# USB3300.net
KiCad netlist of a schematic drawn in EAGLE
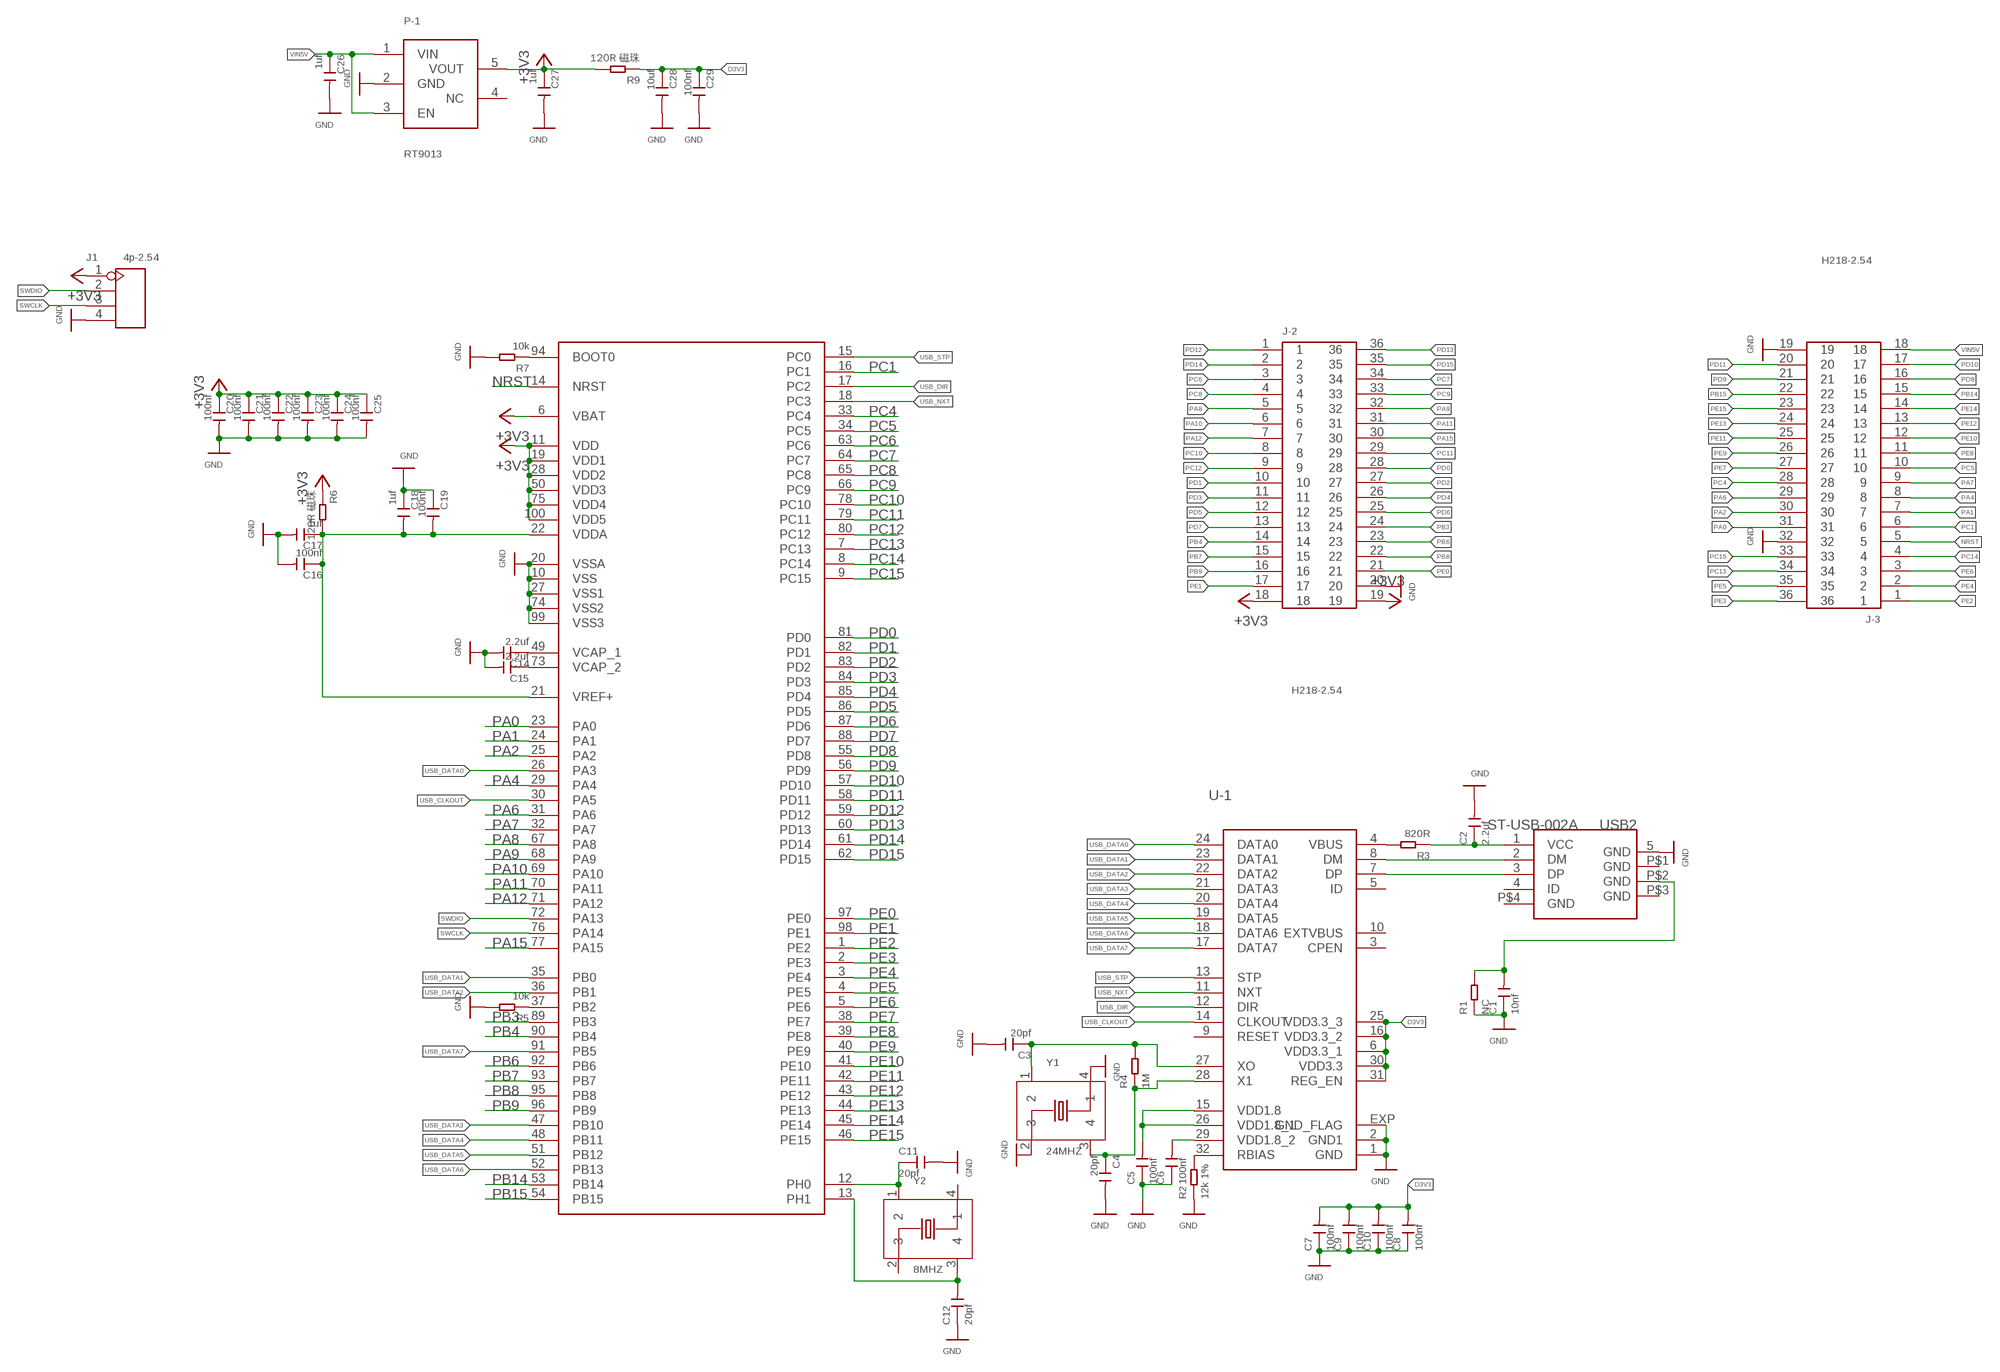
[diagram p0: schematic, sheet 1]

(export (version "E")
  (design (tool "Eeschema 10.0.6"))
  (components
    (comp (ref "C1")
      (value "10nf")
      (footprint "eagle-import:C0603")
      (libsource (lib "eagle-import") (part "CERAMIC-0.5PF-50V-0.1PF-NPO(0603)"))
    )
    (comp (ref "C2")
      (value "2.2uf")
      (footprint "eagle-import:C0603")
      (libsource (lib "eagle-import") (part "CERAMIC-0.5PF-50V-0.1PF-NPO(0603)"))
    )
    (comp (ref "C3")
      (value "20pf")
      (footprint "eagle-import:C0603")
      (libsource (lib "eagle-import") (part "CERAMIC-0.5PF-50V-0.1PF-NPO(0603)"))
    )
    (comp (ref "C4")
      (value "20pf")
      (footprint "eagle-import:C0603")
      (libsource (lib "eagle-import") (part "CERAMIC-0.5PF-50V-0.1PF-NPO(0603)"))
    )
    (comp (ref "C5")
      (value "100nf")
      (footprint "eagle-import:C0603")
      (libsource (lib "eagle-import") (part "CERAMIC-0.5PF-50V-0.1PF-NPO(0603)"))
    )
    (comp (ref "C6")
      (value "100nf")
      (footprint "eagle-import:C0603")
      (libsource (lib "eagle-import") (part "CERAMIC-0.5PF-50V-0.1PF-NPO(0603)"))
    )
    (comp (ref "C7")
      (value "100nf")
      (footprint "eagle-import:C0603")
      (libsource (lib "eagle-import") (part "CERAMIC-0.5PF-50V-0.1PF-NPO(0603)"))
    )
    (comp (ref "C8")
      (value "100nf")
      (footprint "eagle-import:C0603")
      (libsource (lib "eagle-import") (part "CERAMIC-0.5PF-50V-0.1PF-NPO(0603)"))
    )
    (comp (ref "C9")
      (value "100nf")
      (footprint "eagle-import:C0603")
      (libsource (lib "eagle-import") (part "CERAMIC-0.5PF-50V-0.1PF-NPO(0603)"))
    )
    (comp (ref "C10")
      (value "100nf")
      (footprint "eagle-import:C0603")
      (libsource (lib "eagle-import") (part "CERAMIC-0.5PF-50V-0.1PF-NPO(0603)"))
    )
    (comp (ref "C11")
      (value "20pf")
      (footprint "eagle-import:C0603")
      (libsource (lib "eagle-import") (part "CERAMIC-0.5PF-50V-0.1PF-NPO(0603)"))
    )
    (comp (ref "C12")
      (value "20pf")
      (footprint "eagle-import:C0603")
      (libsource (lib "eagle-import") (part "CERAMIC-0.5PF-50V-0.1PF-NPO(0603)"))
    )
    (comp (ref "C14")
      (value "2.2uf")
      (footprint "eagle-import:C0603")
      (libsource (lib "eagle-import") (part "CERAMIC-0.5PF-50V-0.1PF-NPO(0603)"))
    )
    (comp (ref "C15")
      (value "2.2uf")
      (footprint "eagle-import:C0603")
      (libsource (lib "eagle-import") (part "CERAMIC-0.5PF-50V-0.1PF-NPO(0603)"))
    )
    (comp (ref "C16")
      (value "100nf")
      (footprint "eagle-import:C0603")
      (libsource (lib "eagle-import") (part "CERAMIC-0.5PF-50V-0.1PF-NPO(0603)"))
    )
    (comp (ref "C17")
      (value "1uf")
      (footprint "eagle-import:C0603")
      (libsource (lib "eagle-import") (part "CERAMIC-0.5PF-50V-0.1PF-NPO(0603)"))
    )
    (comp (ref "C18")
      (value "1uf")
      (footprint "eagle-import:C0603")
      (libsource (lib "eagle-import") (part "CERAMIC-0.5PF-50V-0.1PF-NPO(0603)"))
    )
    (comp (ref "C19")
      (value "100nf")
      (footprint "eagle-import:C0603")
      (libsource (lib "eagle-import") (part "CERAMIC-0.5PF-50V-0.1PF-NPO(0603)"))
    )
    (comp (ref "C20")
      (value "100nf")
      (footprint "eagle-import:C0603")
      (libsource (lib "eagle-import") (part "CERAMIC-0.5PF-50V-0.1PF-NPO(0603)"))
    )
    (comp (ref "C21")
      (value "100nf")
      (footprint "eagle-import:C0603")
      (libsource (lib "eagle-import") (part "CERAMIC-0.5PF-50V-0.1PF-NPO(0603)"))
    )
    (comp (ref "C22")
      (value "100nf")
      (footprint "eagle-import:C0603")
      (libsource (lib "eagle-import") (part "CERAMIC-0.5PF-50V-0.1PF-NPO(0603)"))
    )
    (comp (ref "C23")
      (value "100nf")
      (footprint "eagle-import:C0603")
      (libsource (lib "eagle-import") (part "CERAMIC-0.5PF-50V-0.1PF-NPO(0603)"))
    )
    (comp (ref "C24")
      (value "100nf")
      (footprint "eagle-import:C0603")
      (libsource (lib "eagle-import") (part "CERAMIC-0.5PF-50V-0.1PF-NPO(0603)"))
    )
    (comp (ref "C25")
      (value "100nf")
      (footprint "eagle-import:C0603")
      (libsource (lib "eagle-import") (part "CERAMIC-0.5PF-50V-0.1PF-NPO(0603)"))
    )
    (comp (ref "C26")
      (value "1uf")
      (footprint "eagle-import:C0603")
      (libsource (lib "eagle-import") (part "CERAMIC-0.5PF-50V-0.1PF-NPO(0603)"))
    )
    (comp (ref "C27")
      (value "1uf")
      (footprint "eagle-import:C0603")
      (libsource (lib "eagle-import") (part "CERAMIC-0.5PF-50V-0.1PF-NPO(0603)"))
    )
    (comp (ref "C28")
      (value "10uf")
      (footprint "eagle-import:C0603")
      (libsource (lib "eagle-import") (part "CERAMIC-0.5PF-50V-0.1PF-NPO(0603)"))
    )
    (comp (ref "C29")
      (value "100nf")
      (footprint "eagle-import:C0603")
      (libsource (lib "eagle-import") (part "CERAMIC-0.5PF-50V-0.1PF-NPO(0603)"))
    )
    (comp (ref "J-2")
      (value "H218-2.54")
      (footprint "eagle-import:H2X18-2.54")
      (libsource (lib "eagle-import") (part "H218-2.54"))
    )
    (comp (ref "J-3")
      (value "H218-2.54")
      (footprint "eagle-import:H2X18-2.54")
      (libsource (lib "eagle-import") (part "H218-2.54"))
    )
    (comp (ref "J1")
      (value "4p-2.54")
      (footprint "eagle-import:H4-2.54")
      (fields (field (name "MPN") "F185-1104A1BSYA1"))
      (libsource (lib "eagle-import") (part "DIP-BLACK-FEMALE-HEADER-VERT(4P-2.54)"))
    )
    (comp (ref "P-1")
      (value "RT9013")
      (footprint "eagle-import:SOT23-5")
      (libsource (lib "eagle-import") (part "RT9013"))
    )
    (comp (ref "R1")
      (value "NC")
      (footprint "eagle-import:R0603")
      (fields (field (name "MPN") "AC0603FR-070RL"))
      (libsource (lib "eagle-import") (part "SMD-RES-0R-1%-1/10W(0603)"))
    )
    (comp (ref "R2")
      (value "12k 1%")
      (footprint "eagle-import:R0603")
      (fields (field (name "MPN") "AC0603FR-070RL"))
      (libsource (lib "eagle-import") (part "SMD-RES-0R-1%-1/10W(0603)"))
    )
    (comp (ref "R3")
      (value "820R")
      (footprint "eagle-import:R0603")
      (fields (field (name "MPN") "AC0603FR-070RL"))
      (libsource (lib "eagle-import") (part "SMD-RES-0R-1%-1/10W(0603)"))
    )
    (comp (ref "R4")
      (value "1M")
      (footprint "eagle-import:R0603")
      (fields (field (name "MPN") "AC0603FR-070RL"))
      (libsource (lib "eagle-import") (part "SMD-RES-0R-1%-1/10W(0603)"))
    )
    (comp (ref "R5")
      (value "10k")
      (footprint "eagle-import:R0603")
      (fields (field (name "MPN") "AC0603FR-070RL"))
      (libsource (lib "eagle-import") (part "SMD-RES-0R-1%-1/10W(0603)"))
    )
    (comp (ref "R6")
      (value "120R 磁珠")
      (footprint "eagle-import:R0603")
      (fields (field (name "MPN") "AC0603FR-070RL"))
      (libsource (lib "eagle-import") (part "SMD-RES-0R-1%-1/10W(0603)"))
    )
    (comp (ref "R7")
      (value "10k")
      (footprint "eagle-import:R0603")
      (fields (field (name "MPN") "AC0603FR-070RL"))
      (libsource (lib "eagle-import") (part "SMD-RES-0R-1%-1/10W(0603)"))
    )
    (comp (ref "R9")
      (value "120R 磁珠")
      (footprint "eagle-import:R0603")
      (fields (field (name "MPN") "AC0603FR-070RL"))
      (libsource (lib "eagle-import") (part "SMD-RES-0R-1%-1/10W(0603)"))
    )
    (comp (ref "U$1")
      (value "STM32F40XSTM32D40X")
      (footprint "eagle-import:LQFP100")
      (libsource (lib "eagle-import") (part "STM32F40XSTM32D40X"))
    )
    (comp (ref "U-1")
      (value "USB3300")
      (footprint "eagle-import:QFN32")
      (libsource (lib "eagle-import") (part "USB3300"))
    )
    (comp (ref "USB2")
      (value "ST-USB-002A")
      (footprint "eagle-import:MINIUSB5+4P-SMD-0.8-90D")
      (libsource (lib "eagle-import") (part "MINI-USB-RCPT-B-5PS-R/A-SMD(ST-USB-002A)"))
    )
    (comp (ref "Y1")
      (value "24MHZ")
      (footprint "eagle-import:X4-SMD-3.2X2.5X0.7MM")
      (fields (field (name "MPN") "7M30000024"))
      (libsource (lib "eagle-import") (part "SMD-CRYSTAL-30MHZ-10PF-10PPM-60R(4P-3.2X2.5MM)"))
    )
    (comp (ref "Y2")
      (value "8MHZ")
      (footprint "eagle-import:X4-SMD-3.2X2.5X0.7MM")
      (fields (field (name "MPN") "7M-27.120MAAJ-T"))
      (libsource (lib "eagle-import") (part "SMD-CRYSTAL-27.12MHZ-18PF-30PPM-60R(4P-3.2X2.5MM)"))
    )
  )
  (nets
    (net (code "1") (name "+3V3") (class "Default")
      (node (ref "C20") (pin "1") (pinfunction "1_1") (pintype "passive"))
      (node (ref "C21") (pin "1") (pinfunction "1_1") (pintype "passive"))
      (node (ref "C22") (pin "1") (pinfunction "1_1") (pintype "passive"))
      (node (ref "C23") (pin "1") (pinfunction "1_1") (pintype "passive"))
      (node (ref "C24") (pin "1") (pinfunction "1_1") (pintype "passive"))
      (node (ref "C25") (pin "1") (pinfunction "1_1") (pintype "passive"))
      (node (ref "C27") (pin "1") (pinfunction "1_1") (pintype "passive"))
      (node (ref "J-2") (pin "18") (pinfunction "18_18") (pintype "bidirectional"))
      (node (ref "J-2") (pin "19") (pinfunction "19_19") (pintype "bidirectional"))
      (node (ref "J1") (pin "1") (pinfunction "P$1_1") (pintype "bidirectional"))
      (node (ref "P-1") (pin "5") (pinfunction "VOUT_5") (pintype "bidirectional"))
      (node (ref "R6") (pin "1") (pinfunction "1_1") (pintype "passive"))
      (node (ref "R9") (pin "2") (pinfunction "2_2") (pintype "passive"))
      (node (ref "U$1") (pin "100") (pinfunction "VDD5_100") (pintype "bidirectional"))
      (node (ref "U$1") (pin "11") (pinfunction "VDD_11") (pintype "bidirectional"))
      (node (ref "U$1") (pin "19") (pinfunction "VDD1_19") (pintype "bidirectional"))
      (node (ref "U$1") (pin "28") (pinfunction "VDD2_28") (pintype "bidirectional"))
      (node (ref "U$1") (pin "50") (pinfunction "VDD3_50") (pintype "bidirectional"))
      (node (ref "U$1") (pin "6") (pinfunction "VBAT_6") (pintype "bidirectional"))
      (node (ref "U$1") (pin "75") (pinfunction "VDD4_75") (pintype "bidirectional"))
    )
    (net (code "2") (name "D3V3") (class "Default")
      (node (ref "C10") (pin "2") (pinfunction "2_2") (pintype "passive"))
      (node (ref "C28") (pin "1") (pinfunction "1_1") (pintype "passive"))
      (node (ref "C29") (pin "1") (pinfunction "1_1") (pintype "passive"))
      (node (ref "C7") (pin "2") (pinfunction "2_2") (pintype "passive"))
      (node (ref "C8") (pin "2") (pinfunction "2_2") (pintype "passive"))
      (node (ref "C9") (pin "2") (pinfunction "2_2") (pintype "passive"))
      (node (ref "R9") (pin "1") (pinfunction "1_1") (pintype "passive"))
      (node (ref "U-1") (pin "16") (pinfunction "VDD3.3_2_16") (pintype "bidirectional"))
      (node (ref "U-1") (pin "25") (pinfunction "VDD3.3_3_25") (pintype "bidirectional"))
      (node (ref "U-1") (pin "30") (pinfunction "VDD3.3_30") (pintype "bidirectional"))
      (node (ref "U-1") (pin "31") (pinfunction "REG_EN_31") (pintype "bidirectional"))
      (node (ref "U-1") (pin "6") (pinfunction "VDD3.3_1_6") (pintype "bidirectional"))
    )
    (net (code "3") (name "GND") (class "Default")
      (node (ref "C1") (pin "1") (pinfunction "1_1") (pintype "passive"))
      (node (ref "C10") (pin "1") (pinfunction "1_1") (pintype "passive"))
      (node (ref "C11") (pin "2") (pinfunction "2_2") (pintype "passive"))
      (node (ref "C12") (pin "1") (pinfunction "1_1") (pintype "passive"))
      (node (ref "C14") (pin "2") (pinfunction "2_2") (pintype "passive"))
      (node (ref "C15") (pin "2") (pinfunction "2_2") (pintype "passive"))
      (node (ref "C16") (pin "2") (pinfunction "2_2") (pintype "passive"))
      (node (ref "C17") (pin "2") (pinfunction "2_2") (pintype "passive"))
      (node (ref "C18") (pin "1") (pinfunction "1_1") (pintype "passive"))
      (node (ref "C19") (pin "1") (pinfunction "1_1") (pintype "passive"))
      (node (ref "C2") (pin "2") (pinfunction "2_2") (pintype "passive"))
      (node (ref "C20") (pin "2") (pinfunction "2_2") (pintype "passive"))
      (node (ref "C21") (pin "2") (pinfunction "2_2") (pintype "passive"))
      (node (ref "C22") (pin "2") (pinfunction "2_2") (pintype "passive"))
      (node (ref "C23") (pin "2") (pinfunction "2_2") (pintype "passive"))
      (node (ref "C24") (pin "2") (pinfunction "2_2") (pintype "passive"))
      (node (ref "C25") (pin "2") (pinfunction "2_2") (pintype "passive"))
      (node (ref "C26") (pin "2") (pinfunction "2_2") (pintype "passive"))
      (node (ref "C27") (pin "2") (pinfunction "2_2") (pintype "passive"))
      (node (ref "C28") (pin "2") (pinfunction "2_2") (pintype "passive"))
      (node (ref "C29") (pin "2") (pinfunction "2_2") (pintype "passive"))
      (node (ref "C3") (pin "2") (pinfunction "2_2") (pintype "passive"))
      (node (ref "C4") (pin "2") (pinfunction "2_2") (pintype "passive"))
      (node (ref "C5") (pin "1") (pinfunction "1_1") (pintype "passive"))
      (node (ref "C6") (pin "1") (pinfunction "1_1") (pintype "passive"))
      (node (ref "C7") (pin "1") (pinfunction "1_1") (pintype "passive"))
      (node (ref "C8") (pin "1") (pinfunction "1_1") (pintype "passive"))
      (node (ref "C9") (pin "1") (pinfunction "1_1") (pintype "passive"))
      (node (ref "J-2") (pin "20") (pinfunction "20_20") (pintype "bidirectional"))
      (node (ref "J-3") (pin "19") (pinfunction "19_19") (pintype "bidirectional"))
      (node (ref "J-3") (pin "32") (pinfunction "32_32") (pintype "bidirectional"))
      (node (ref "J1") (pin "4") (pinfunction "P$4_4") (pintype "bidirectional"))
      (node (ref "P-1") (pin "2") (pinfunction "GND_2") (pintype "bidirectional"))
      (node (ref "R1") (pin "1") (pinfunction "1_1") (pintype "passive"))
      (node (ref "R2") (pin "1") (pinfunction "1_1") (pintype "passive"))
      (node (ref "R5") (pin "2") (pinfunction "2_2") (pintype "passive"))
      (node (ref "R7") (pin "2") (pinfunction "2_2") (pintype "passive"))
      (node (ref "U$1") (pin "10") (pinfunction "VSS_10") (pintype "bidirectional"))
      (node (ref "U$1") (pin "20") (pinfunction "VSSA_20") (pintype "bidirectional"))
      (node (ref "U$1") (pin "27") (pinfunction "VSS1_27") (pintype "bidirectional"))
      (node (ref "U$1") (pin "74") (pinfunction "VSS2_74") (pintype "bidirectional"))
      (node (ref "U$1") (pin "99") (pinfunction "VSS3_99") (pintype "bidirectional"))
      (node (ref "U-1") (pin "1") (pinfunction "GND_1") (pintype "bidirectional"))
      (node (ref "U-1") (pin "2") (pinfunction "GND1_2") (pintype "bidirectional"))
      (node (ref "U-1") (pin "EXP") (pinfunction "GND_FLAG_EXP") (pintype "bidirectional"))
      (node (ref "USB2") (pin "5") (pinfunction "GND_5") (pintype "bidirectional"))
      (node (ref "Y1") (pin "2") (pinfunction "3_2") (pintype "bidirectional"))
      (node (ref "Y1") (pin "4") (pinfunction "1_4") (pintype "bidirectional"))
    )
    (net (code "4") (name "NRST") (class "Default")
      (node (ref "J-3") (pin "5") (pinfunction "5_5") (pintype "bidirectional"))
      (node (ref "U$1") (pin "14") (pinfunction "NRST_14") (pintype "bidirectional"))
    )
    (net (code "5") (name "Net-(C1-Pad2)") (class "Default")
      (node (ref "C1") (pin "2") (pinfunction "2_2") (pintype "passive"))
      (node (ref "R1") (pin "2") (pinfunction "2_2") (pintype "passive"))
      (node (ref "USB2") (pin "P$2") (pinfunction "GND_P$2") (pintype "bidirectional"))
    )
    (net (code "6") (name "Net-(U$1-BOOT0)") (class "Default")
      (node (ref "R7") (pin "1") (pinfunction "1_1") (pintype "passive"))
      (node (ref "U$1") (pin "94") (pinfunction "BOOT0_94") (pintype "bidirectional"))
    )
    (net (code "7") (name "Net-(U$1-PB2)") (class "Default")
      (node (ref "R5") (pin "1") (pinfunction "1_1") (pintype "passive"))
      (node (ref "U$1") (pin "37") (pinfunction "PB2_37") (pintype "bidirectional"))
    )
    (net (code "8") (name "Net-(U$1-PH0)") (class "Default")
      (node (ref "C11") (pin "1") (pinfunction "1_1") (pintype "passive"))
      (node (ref "U$1") (pin "12") (pinfunction "PH0_12") (pintype "bidirectional"))
      (node (ref "Y2") (pin "1") (pinfunction "2_1") (pintype "bidirectional"))
    )
    (net (code "9") (name "Net-(U$1-PH1)") (class "Default")
      (node (ref "C12") (pin "2") (pinfunction "2_2") (pintype "passive"))
      (node (ref "U$1") (pin "13") (pinfunction "PH1_13") (pintype "bidirectional"))
      (node (ref "Y2") (pin "3") (pinfunction "4_3") (pintype "bidirectional"))
    )
    (net (code "10") (name "Net-(U$1-VCAP_1)") (class "Default")
      (node (ref "C14") (pin "1") (pinfunction "1_1") (pintype "passive"))
      (node (ref "U$1") (pin "49") (pinfunction "VCAP_1_49") (pintype "bidirectional"))
    )
    (net (code "11") (name "Net-(U$1-VCAP_2)") (class "Default")
      (node (ref "C15") (pin "1") (pinfunction "1_1") (pintype "passive"))
      (node (ref "U$1") (pin "73") (pinfunction "VCAP_2_73") (pintype "bidirectional"))
    )
    (net (code "12") (name "Net-(U$1-VDDA)") (class "Default")
      (node (ref "C16") (pin "1") (pinfunction "1_1") (pintype "passive"))
      (node (ref "C17") (pin "1") (pinfunction "1_1") (pintype "passive"))
      (node (ref "C18") (pin "2") (pinfunction "2_2") (pintype "passive"))
      (node (ref "C19") (pin "2") (pinfunction "2_2") (pintype "passive"))
      (node (ref "R6") (pin "2") (pinfunction "2_2") (pintype "passive"))
      (node (ref "U$1") (pin "21") (pinfunction "VREF+_21") (pintype "bidirectional"))
      (node (ref "U$1") (pin "22") (pinfunction "VDDA_22") (pintype "bidirectional"))
    )
    (net (code "13") (name "Net-(U-1-DM)") (class "Default")
      (node (ref "U-1") (pin "8") (pinfunction "DM_8") (pintype "bidirectional"))
      (node (ref "USB2") (pin "2") (pinfunction "DM_2") (pintype "bidirectional"))
    )
    (net (code "14") (name "Net-(U-1-DP)") (class "Default")
      (node (ref "U-1") (pin "7") (pinfunction "DP_7") (pintype "bidirectional"))
      (node (ref "USB2") (pin "3") (pinfunction "DP_3") (pintype "bidirectional"))
    )
    (net (code "15") (name "Net-(U-1-RBIAS)") (class "Default")
      (node (ref "R2") (pin "2") (pinfunction "2_2") (pintype "passive"))
      (node (ref "U-1") (pin "32") (pinfunction "RBIAS_32") (pintype "bidirectional"))
    )
    (net (code "16") (name "Net-(U-1-VBUS)") (class "Default")
      (node (ref "R3") (pin "2") (pinfunction "2_2") (pintype "passive"))
      (node (ref "U-1") (pin "4") (pinfunction "VBUS_4") (pintype "bidirectional"))
    )
    (net (code "17") (name "Net-(U-1-VDD1.8)") (class "Default")
      (node (ref "C5") (pin "2") (pinfunction "2_2") (pintype "passive"))
      (node (ref "U-1") (pin "15") (pinfunction "VDD1.8_15") (pintype "bidirectional"))
      (node (ref "U-1") (pin "26") (pinfunction "VDD1.8_1_26") (pintype "bidirectional"))
    )
    (net (code "18") (name "Net-(U-1-VDD1.8_2)") (class "Default")
      (node (ref "C6") (pin "2") (pinfunction "2_2") (pintype "passive"))
      (node (ref "U-1") (pin "29") (pinfunction "VDD1.8_2_29") (pintype "bidirectional"))
    )
    (net (code "19") (name "Net-(U-1-X1)") (class "Default")
      (node (ref "C4") (pin "1") (pinfunction "1_1") (pintype "passive"))
      (node (ref "R4") (pin "1") (pinfunction "1_1") (pintype "passive"))
      (node (ref "U-1") (pin "28") (pinfunction "X1_28") (pintype "bidirectional"))
      (node (ref "Y1") (pin "3") (pinfunction "4_3") (pintype "bidirectional"))
    )
    (net (code "20") (name "Net-(U-1-XO)") (class "Default")
      (node (ref "C3") (pin "1") (pinfunction "1_1") (pintype "passive"))
      (node (ref "R4") (pin "2") (pinfunction "2_2") (pintype "passive"))
      (node (ref "U-1") (pin "27") (pinfunction "XO_27") (pintype "bidirectional"))
      (node (ref "Y1") (pin "1") (pinfunction "2_1") (pintype "bidirectional"))
    )
    (net (code "21") (name "Net-(USB2-VCC)") (class "Default")
      (node (ref "C2") (pin "1") (pinfunction "1_1") (pintype "passive"))
      (node (ref "R3") (pin "1") (pinfunction "1_1") (pintype "passive"))
      (node (ref "USB2") (pin "1") (pinfunction "VCC_1") (pintype "bidirectional"))
    )
    (net (code "22") (name "PA0") (class "Default")
      (node (ref "J-3") (pin "31") (pinfunction "31_31") (pintype "bidirectional"))
      (node (ref "U$1") (pin "23") (pinfunction "PA0_23") (pintype "bidirectional"))
    )
    (net (code "23") (name "PA1") (class "Default")
      (node (ref "J-3") (pin "7") (pinfunction "7_7") (pintype "bidirectional"))
      (node (ref "U$1") (pin "24") (pinfunction "PA1_24") (pintype "bidirectional"))
    )
    (net (code "24") (name "PA2") (class "Default")
      (node (ref "J-3") (pin "30") (pinfunction "30_30") (pintype "bidirectional"))
      (node (ref "U$1") (pin "25") (pinfunction "PA2_25") (pintype "bidirectional"))
    )
    (net (code "25") (name "PA4") (class "Default")
      (node (ref "J-3") (pin "8") (pinfunction "8_8") (pintype "bidirectional"))
      (node (ref "U$1") (pin "29") (pinfunction "PA4_29") (pintype "bidirectional"))
    )
    (net (code "26") (name "PA6") (class "Default")
      (node (ref "J-3") (pin "29") (pinfunction "29_29") (pintype "bidirectional"))
      (node (ref "U$1") (pin "31") (pinfunction "PA6_31") (pintype "bidirectional"))
    )
    (net (code "27") (name "PA7") (class "Default")
      (node (ref "J-3") (pin "9") (pinfunction "9_9") (pintype "bidirectional"))
      (node (ref "U$1") (pin "32") (pinfunction "PA7_32") (pintype "bidirectional"))
    )
    (net (code "28") (name "PA8") (class "Default")
      (node (ref "J-2") (pin "5") (pinfunction "5_5") (pintype "bidirectional"))
      (node (ref "U$1") (pin "67") (pinfunction "PA8_67") (pintype "bidirectional"))
    )
    (net (code "29") (name "PA9") (class "Default")
      (node (ref "J-2") (pin "32") (pinfunction "32_32") (pintype "bidirectional"))
      (node (ref "U$1") (pin "68") (pinfunction "PA9_68") (pintype "bidirectional"))
    )
    (net (code "30") (name "PA10") (class "Default")
      (node (ref "J-2") (pin "6") (pinfunction "6_6") (pintype "bidirectional"))
      (node (ref "U$1") (pin "69") (pinfunction "PA10_69") (pintype "bidirectional"))
    )
    (net (code "31") (name "PA11") (class "Default")
      (node (ref "J-2") (pin "31") (pinfunction "31_31") (pintype "bidirectional"))
      (node (ref "U$1") (pin "70") (pinfunction "PA11_70") (pintype "bidirectional"))
    )
    (net (code "32") (name "PA12") (class "Default")
      (node (ref "J-2") (pin "7") (pinfunction "7_7") (pintype "bidirectional"))
      (node (ref "U$1") (pin "71") (pinfunction "PA12_71") (pintype "bidirectional"))
    )
    (net (code "33") (name "PA15") (class "Default")
      (node (ref "J-2") (pin "30") (pinfunction "30_30") (pintype "bidirectional"))
      (node (ref "U$1") (pin "77") (pinfunction "PA15_77") (pintype "bidirectional"))
    )
    (net (code "34") (name "PB3") (class "Default")
      (node (ref "J-2") (pin "24") (pinfunction "24_24") (pintype "bidirectional"))
      (node (ref "U$1") (pin "89") (pinfunction "PB3_89") (pintype "bidirectional"))
    )
    (net (code "35") (name "PB4") (class "Default")
      (node (ref "J-2") (pin "14") (pinfunction "14_14") (pintype "bidirectional"))
      (node (ref "U$1") (pin "90") (pinfunction "PB4_90") (pintype "bidirectional"))
    )
    (net (code "36") (name "PB6") (class "Default")
      (node (ref "J-2") (pin "23") (pinfunction "23_23") (pintype "bidirectional"))
      (node (ref "U$1") (pin "92") (pinfunction "PB6_92") (pintype "bidirectional"))
    )
    (net (code "37") (name "PB7") (class "Default")
      (node (ref "J-2") (pin "15") (pinfunction "15_15") (pintype "bidirectional"))
      (node (ref "U$1") (pin "93") (pinfunction "PB7_93") (pintype "bidirectional"))
    )
    (net (code "38") (name "PB8") (class "Default")
      (node (ref "J-2") (pin "22") (pinfunction "22_22") (pintype "bidirectional"))
      (node (ref "U$1") (pin "95") (pinfunction "PB8_95") (pintype "bidirectional"))
    )
    (net (code "39") (name "PB9") (class "Default")
      (node (ref "J-2") (pin "16") (pinfunction "16_16") (pintype "bidirectional"))
      (node (ref "U$1") (pin "96") (pinfunction "PB9_96") (pintype "bidirectional"))
    )
    (net (code "40") (name "PB14") (class "Default")
      (node (ref "J-3") (pin "15") (pinfunction "15_15") (pintype "bidirectional"))
      (node (ref "U$1") (pin "53") (pinfunction "PB14_53") (pintype "bidirectional"))
    )
    (net (code "41") (name "PB15") (class "Default")
      (node (ref "J-3") (pin "22") (pinfunction "22_22") (pintype "bidirectional"))
      (node (ref "U$1") (pin "54") (pinfunction "PB15_54") (pintype "bidirectional"))
    )
    (net (code "42") (name "PC1") (class "Default")
      (node (ref "J-3") (pin "6") (pinfunction "6_6") (pintype "bidirectional"))
      (node (ref "U$1") (pin "16") (pinfunction "PC1_16") (pintype "bidirectional"))
    )
    (net (code "43") (name "PC4") (class "Default")
      (node (ref "J-3") (pin "28") (pinfunction "28_28") (pintype "bidirectional"))
      (node (ref "U$1") (pin "33") (pinfunction "PC4_33") (pintype "bidirectional"))
    )
    (net (code "44") (name "PC5") (class "Default")
      (node (ref "J-3") (pin "10") (pinfunction "10_10") (pintype "bidirectional"))
      (node (ref "U$1") (pin "34") (pinfunction "PC5_34") (pintype "bidirectional"))
    )
    (net (code "45") (name "PC6") (class "Default")
      (node (ref "J-2") (pin "3") (pinfunction "3_3") (pintype "bidirectional"))
      (node (ref "U$1") (pin "63") (pinfunction "PC6_63") (pintype "bidirectional"))
    )
    (net (code "46") (name "PC7") (class "Default")
      (node (ref "J-2") (pin "34") (pinfunction "34_34") (pintype "bidirectional"))
      (node (ref "U$1") (pin "64") (pinfunction "PC7_64") (pintype "bidirectional"))
    )
    (net (code "47") (name "PC8") (class "Default")
      (node (ref "J-2") (pin "4") (pinfunction "4_4") (pintype "bidirectional"))
      (node (ref "U$1") (pin "65") (pinfunction "PC8_65") (pintype "bidirectional"))
    )
    (net (code "48") (name "PC9") (class "Default")
      (node (ref "J-2") (pin "33") (pinfunction "33_33") (pintype "bidirectional"))
      (node (ref "U$1") (pin "66") (pinfunction "PC9_66") (pintype "bidirectional"))
    )
    (net (code "49") (name "PC10") (class "Default")
      (node (ref "J-2") (pin "8") (pinfunction "8_8") (pintype "bidirectional"))
      (node (ref "U$1") (pin "78") (pinfunction "PC10_78") (pintype "bidirectional"))
    )
    (net (code "50") (name "PC11") (class "Default")
      (node (ref "J-2") (pin "29") (pinfunction "29_29") (pintype "bidirectional"))
      (node (ref "U$1") (pin "79") (pinfunction "PC11_79") (pintype "bidirectional"))
    )
    (net (code "51") (name "PC12") (class "Default")
      (node (ref "J-2") (pin "9") (pinfunction "9_9") (pintype "bidirectional"))
      (node (ref "U$1") (pin "80") (pinfunction "PC12_80") (pintype "bidirectional"))
    )
    (net (code "52") (name "PC13") (class "Default")
      (node (ref "J-3") (pin "34") (pinfunction "34_34") (pintype "bidirectional"))
      (node (ref "U$1") (pin "7") (pinfunction "PC13_7") (pintype "bidirectional"))
    )
    (net (code "53") (name "PC14") (class "Default")
      (node (ref "J-3") (pin "4") (pinfunction "4_4") (pintype "bidirectional"))
      (node (ref "U$1") (pin "8") (pinfunction "PC14_8") (pintype "bidirectional"))
    )
    (net (code "54") (name "PC15") (class "Default")
      (node (ref "J-3") (pin "33") (pinfunction "33_33") (pintype "bidirectional"))
      (node (ref "U$1") (pin "9") (pinfunction "PC15_9") (pintype "bidirectional"))
    )
    (net (code "55") (name "PD0") (class "Default")
      (node (ref "J-2") (pin "28") (pinfunction "28_28") (pintype "bidirectional"))
      (node (ref "U$1") (pin "81") (pinfunction "PD0_81") (pintype "bidirectional"))
    )
    (net (code "56") (name "PD1") (class "Default")
      (node (ref "J-2") (pin "10") (pinfunction "10_10") (pintype "bidirectional"))
      (node (ref "U$1") (pin "82") (pinfunction "PD1_82") (pintype "bidirectional"))
    )
    (net (code "57") (name "PD2") (class "Default")
      (node (ref "J-2") (pin "27") (pinfunction "27_27") (pintype "bidirectional"))
      (node (ref "U$1") (pin "83") (pinfunction "PD2_83") (pintype "bidirectional"))
    )
    (net (code "58") (name "PD3") (class "Default")
      (node (ref "J-2") (pin "11") (pinfunction "11_11") (pintype "bidirectional"))
      (node (ref "U$1") (pin "84") (pinfunction "PD3_84") (pintype "bidirectional"))
    )
    (net (code "59") (name "PD4") (class "Default")
      (node (ref "J-2") (pin "26") (pinfunction "26_26") (pintype "bidirectional"))
      (node (ref "U$1") (pin "85") (pinfunction "PD4_85") (pintype "bidirectional"))
    )
    (net (code "60") (name "PD5") (class "Default")
      (node (ref "J-2") (pin "12") (pinfunction "12_12") (pintype "bidirectional"))
      (node (ref "U$1") (pin "86") (pinfunction "PD5_86") (pintype "bidirectional"))
    )
    (net (code "61") (name "PD6") (class "Default")
      (node (ref "J-2") (pin "25") (pinfunction "25_25") (pintype "bidirectional"))
      (node (ref "U$1") (pin "87") (pinfunction "PD6_87") (pintype "bidirectional"))
    )
    (net (code "62") (name "PD7") (class "Default")
      (node (ref "J-2") (pin "13") (pinfunction "13_13") (pintype "bidirectional"))
      (node (ref "U$1") (pin "88") (pinfunction "PD7_88") (pintype "bidirectional"))
    )
    (net (code "63") (name "PD8") (class "Default")
      (node (ref "J-3") (pin "16") (pinfunction "16_16") (pintype "bidirectional"))
      (node (ref "U$1") (pin "55") (pinfunction "PD8_55") (pintype "bidirectional"))
    )
    (net (code "64") (name "PD9") (class "Default")
      (node (ref "J-3") (pin "21") (pinfunction "21_21") (pintype "bidirectional"))
      (node (ref "U$1") (pin "56") (pinfunction "PD9_56") (pintype "bidirectional"))
    )
    (net (code "65") (name "PD10") (class "Default")
      (node (ref "J-3") (pin "17") (pinfunction "17_17") (pintype "bidirectional"))
      (node (ref "U$1") (pin "57") (pinfunction "PD10_57") (pintype "bidirectional"))
    )
    (net (code "66") (name "PD11") (class "Default")
      (node (ref "J-3") (pin "20") (pinfunction "20_20") (pintype "bidirectional"))
      (node (ref "U$1") (pin "58") (pinfunction "PD11_58") (pintype "bidirectional"))
    )
    (net (code "67") (name "PD12") (class "Default")
      (node (ref "J-2") (pin "1") (pinfunction "1_1") (pintype "bidirectional"))
      (node (ref "U$1") (pin "59") (pinfunction "PD12_59") (pintype "bidirectional"))
    )
    (net (code "68") (name "PD13") (class "Default")
      (node (ref "J-2") (pin "36") (pinfunction "36_36") (pintype "bidirectional"))
      (node (ref "U$1") (pin "60") (pinfunction "PD13_60") (pintype "bidirectional"))
    )
    (net (code "69") (name "PD14") (class "Default")
      (node (ref "J-2") (pin "2") (pinfunction "2_2") (pintype "bidirectional"))
      (node (ref "U$1") (pin "61") (pinfunction "PD14_61") (pintype "bidirectional"))
    )
    (net (code "70") (name "PD15") (class "Default")
      (node (ref "J-2") (pin "35") (pinfunction "35_35") (pintype "bidirectional"))
      (node (ref "U$1") (pin "62") (pinfunction "PD15_62") (pintype "bidirectional"))
    )
    (net (code "71") (name "PE0") (class "Default")
      (node (ref "J-2") (pin "21") (pinfunction "21_21") (pintype "bidirectional"))
      (node (ref "U$1") (pin "97") (pinfunction "PE0_97") (pintype "bidirectional"))
    )
    (net (code "72") (name "PE1") (class "Default")
      (node (ref "J-2") (pin "17") (pinfunction "17_17") (pintype "bidirectional"))
      (node (ref "U$1") (pin "98") (pinfunction "PE1_98") (pintype "bidirectional"))
    )
    (net (code "73") (name "PE2") (class "Default")
      (node (ref "J-3") (pin "1") (pinfunction "1_1") (pintype "bidirectional"))
      (node (ref "U$1") (pin "1") (pinfunction "PE2_1") (pintype "bidirectional"))
    )
    (net (code "74") (name "PE3") (class "Default")
      (node (ref "J-3") (pin "36") (pinfunction "36_36") (pintype "bidirectional"))
      (node (ref "U$1") (pin "2") (pinfunction "PE3_2") (pintype "bidirectional"))
    )
    (net (code "75") (name "PE4") (class "Default")
      (node (ref "J-3") (pin "2") (pinfunction "2_2") (pintype "bidirectional"))
      (node (ref "U$1") (pin "3") (pinfunction "PE4_3") (pintype "bidirectional"))
    )
    (net (code "76") (name "PE5") (class "Default")
      (node (ref "J-3") (pin "35") (pinfunction "35_35") (pintype "bidirectional"))
      (node (ref "U$1") (pin "4") (pinfunction "PE5_4") (pintype "bidirectional"))
    )
    (net (code "77") (name "PE6") (class "Default")
      (node (ref "J-3") (pin "3") (pinfunction "3_3") (pintype "bidirectional"))
      (node (ref "U$1") (pin "5") (pinfunction "PE6_5") (pintype "bidirectional"))
    )
    (net (code "78") (name "PE7") (class "Default")
      (node (ref "J-3") (pin "27") (pinfunction "27_27") (pintype "bidirectional"))
      (node (ref "U$1") (pin "38") (pinfunction "PE7_38") (pintype "bidirectional"))
    )
    (net (code "79") (name "PE8") (class "Default")
      (node (ref "J-3") (pin "11") (pinfunction "11_11") (pintype "bidirectional"))
      (node (ref "U$1") (pin "39") (pinfunction "PE8_39") (pintype "bidirectional"))
    )
    (net (code "80") (name "PE9") (class "Default")
      (node (ref "J-3") (pin "26") (pinfunction "26_26") (pintype "bidirectional"))
      (node (ref "U$1") (pin "40") (pinfunction "PE9_40") (pintype "bidirectional"))
    )
    (net (code "81") (name "PE10") (class "Default")
      (node (ref "J-3") (pin "12") (pinfunction "12_12") (pintype "bidirectional"))
      (node (ref "U$1") (pin "41") (pinfunction "PE10_41") (pintype "bidirectional"))
    )
    (net (code "82") (name "PE11") (class "Default")
      (node (ref "J-3") (pin "25") (pinfunction "25_25") (pintype "bidirectional"))
      (node (ref "U$1") (pin "42") (pinfunction "PE11_42") (pintype "bidirectional"))
    )
    (net (code "83") (name "PE12") (class "Default")
      (node (ref "J-3") (pin "13") (pinfunction "13_13") (pintype "bidirectional"))
      (node (ref "U$1") (pin "43") (pinfunction "PE12_43") (pintype "bidirectional"))
    )
    (net (code "84") (name "PE13") (class "Default")
      (node (ref "J-3") (pin "24") (pinfunction "24_24") (pintype "bidirectional"))
      (node (ref "U$1") (pin "44") (pinfunction "PE13_44") (pintype "bidirectional"))
    )
    (net (code "85") (name "PE14") (class "Default")
      (node (ref "J-3") (pin "14") (pinfunction "14_14") (pintype "bidirectional"))
      (node (ref "U$1") (pin "45") (pinfunction "PE14_45") (pintype "bidirectional"))
    )
    (net (code "86") (name "PE15") (class "Default")
      (node (ref "J-3") (pin "23") (pinfunction "23_23") (pintype "bidirectional"))
      (node (ref "U$1") (pin "46") (pinfunction "PE15_46") (pintype "bidirectional"))
    )
    (net (code "87") (name "SWCLK") (class "Default")
      (node (ref "J1") (pin "3") (pinfunction "P$3_3") (pintype "bidirectional"))
      (node (ref "U$1") (pin "76") (pinfunction "PA14_76") (pintype "bidirectional"))
    )
    (net (code "88") (name "SWDIO") (class "Default")
      (node (ref "J1") (pin "2") (pinfunction "P$2_2") (pintype "bidirectional"))
      (node (ref "U$1") (pin "72") (pinfunction "PA13_72") (pintype "bidirectional"))
    )
    (net (code "89") (name "USB_CLKOUT") (class "Default")
      (node (ref "U$1") (pin "30") (pinfunction "PA5_30") (pintype "bidirectional"))
      (node (ref "U-1") (pin "14") (pinfunction "CLKOUT_14") (pintype "bidirectional"))
    )
    (net (code "90") (name "USB_DATA0") (class "Default")
      (node (ref "U$1") (pin "26") (pinfunction "PA3_26") (pintype "bidirectional"))
      (node (ref "U-1") (pin "24") (pinfunction "DATA0_24") (pintype "bidirectional"))
    )
    (net (code "91") (name "USB_DATA1") (class "Default")
      (node (ref "U$1") (pin "35") (pinfunction "PB0_35") (pintype "bidirectional"))
      (node (ref "U-1") (pin "23") (pinfunction "DATA1_23") (pintype "bidirectional"))
    )
    (net (code "92") (name "USB_DATA2") (class "Default")
      (node (ref "U$1") (pin "36") (pinfunction "PB1_36") (pintype "bidirectional"))
      (node (ref "U-1") (pin "22") (pinfunction "DATA2_22") (pintype "bidirectional"))
    )
    (net (code "93") (name "USB_DATA3") (class "Default")
      (node (ref "U$1") (pin "47") (pinfunction "PB10_47") (pintype "bidirectional"))
      (node (ref "U-1") (pin "21") (pinfunction "DATA3_21") (pintype "bidirectional"))
    )
    (net (code "94") (name "USB_DATA4") (class "Default")
      (node (ref "U$1") (pin "48") (pinfunction "PB11_48") (pintype "bidirectional"))
      (node (ref "U-1") (pin "20") (pinfunction "DATA4_20") (pintype "bidirectional"))
    )
    (net (code "95") (name "USB_DATA5") (class "Default")
      (node (ref "U$1") (pin "51") (pinfunction "PB12_51") (pintype "bidirectional"))
      (node (ref "U-1") (pin "19") (pinfunction "DATA5_19") (pintype "bidirectional"))
    )
    (net (code "96") (name "USB_DATA6") (class "Default")
      (node (ref "U$1") (pin "52") (pinfunction "PB13_52") (pintype "bidirectional"))
      (node (ref "U-1") (pin "18") (pinfunction "DATA6_18") (pintype "bidirectional"))
    )
    (net (code "97") (name "USB_DATA7") (class "Default")
      (node (ref "U$1") (pin "91") (pinfunction "PB5_91") (pintype "bidirectional"))
      (node (ref "U-1") (pin "17") (pinfunction "DATA7_17") (pintype "bidirectional"))
    )
    (net (code "98") (name "USB_DIR") (class "Default")
      (node (ref "U$1") (pin "17") (pinfunction "PC2_17") (pintype "bidirectional"))
      (node (ref "U-1") (pin "12") (pinfunction "DIR_12") (pintype "bidirectional"))
    )
    (net (code "99") (name "USB_NXT") (class "Default")
      (node (ref "U$1") (pin "18") (pinfunction "PC3_18") (pintype "bidirectional"))
      (node (ref "U-1") (pin "11") (pinfunction "NXT_11") (pintype "bidirectional"))
    )
    (net (code "100") (name "USB_STP") (class "Default")
      (node (ref "U$1") (pin "15") (pinfunction "PC0_15") (pintype "bidirectional"))
      (node (ref "U-1") (pin "13") (pinfunction "STP_13") (pintype "bidirectional"))
    )
    (net (code "101") (name "VIN5V") (class "Default")
      (node (ref "C26") (pin "1") (pinfunction "1_1") (pintype "passive"))
      (node (ref "J-3") (pin "18") (pinfunction "18_18") (pintype "bidirectional"))
      (node (ref "P-1") (pin "1") (pinfunction "VIN_1") (pintype "bidirectional"))
      (node (ref "P-1") (pin "3") (pinfunction "EN_3") (pintype "bidirectional"))
    )
    (net (code "102") (name "unconnected-(P-1-NC-Pad4)") (class "Default")
      (node (ref "P-1") (pin "4") (pinfunction "NC_4") (pintype "bidirectional"))
    )
    (net (code "103") (name "unconnected-(U-1-CPEN-Pad3)") (class "Default")
      (node (ref "U-1") (pin "3") (pinfunction "CPEN_3") (pintype "bidirectional"))
    )
    (net (code "104") (name "unconnected-(U-1-EXTVBUS-Pad10)") (class "Default")
      (node (ref "U-1") (pin "10") (pinfunction "EXTVBUS_10") (pintype "bidirectional"))
    )
    (net (code "105") (name "unconnected-(U-1-ID-Pad5)") (class "Default")
      (node (ref "U-1") (pin "5") (pinfunction "ID_5") (pintype "bidirectional"))
    )
    (net (code "106") (name "unconnected-(U-1-RESET-Pad9)") (class "Default")
      (node (ref "U-1") (pin "9") (pinfunction "RESET_9") (pintype "bidirectional"))
    )
    (net (code "107") (name "unconnected-(USB2-GND-PadP$1)") (class "Default")
      (node (ref "USB2") (pin "P$1") (pinfunction "GND_P$1") (pintype "bidirectional"))
    )
    (net (code "108") (name "unconnected-(USB2-GND-PadP$3)") (class "Default")
      (node (ref "USB2") (pin "P$3") (pinfunction "GND_P$3") (pintype "bidirectional"))
    )
    (net (code "109") (name "unconnected-(USB2-GND-PadP$4)") (class "Default")
      (node (ref "USB2") (pin "P$4") (pinfunction "GND_P$4") (pintype "bidirectional"))
    )
    (net (code "110") (name "unconnected-(USB2-ID-Pad4)") (class "Default")
      (node (ref "USB2") (pin "4") (pinfunction "ID_4") (pintype "bidirectional"))
    )
    (net (code "111") (name "unconnected-(Y2-1-Pad4)") (class "Default")
      (node (ref "Y2") (pin "4") (pinfunction "1_4") (pintype "bidirectional"))
    )
    (net (code "112") (name "unconnected-(Y2-3-Pad2)") (class "Default")
      (node (ref "Y2") (pin "2") (pinfunction "3_2") (pintype "bidirectional"))
    )
  )
)
